# Adder.net
KiCad netlist of a schematic drawn in EAGLE
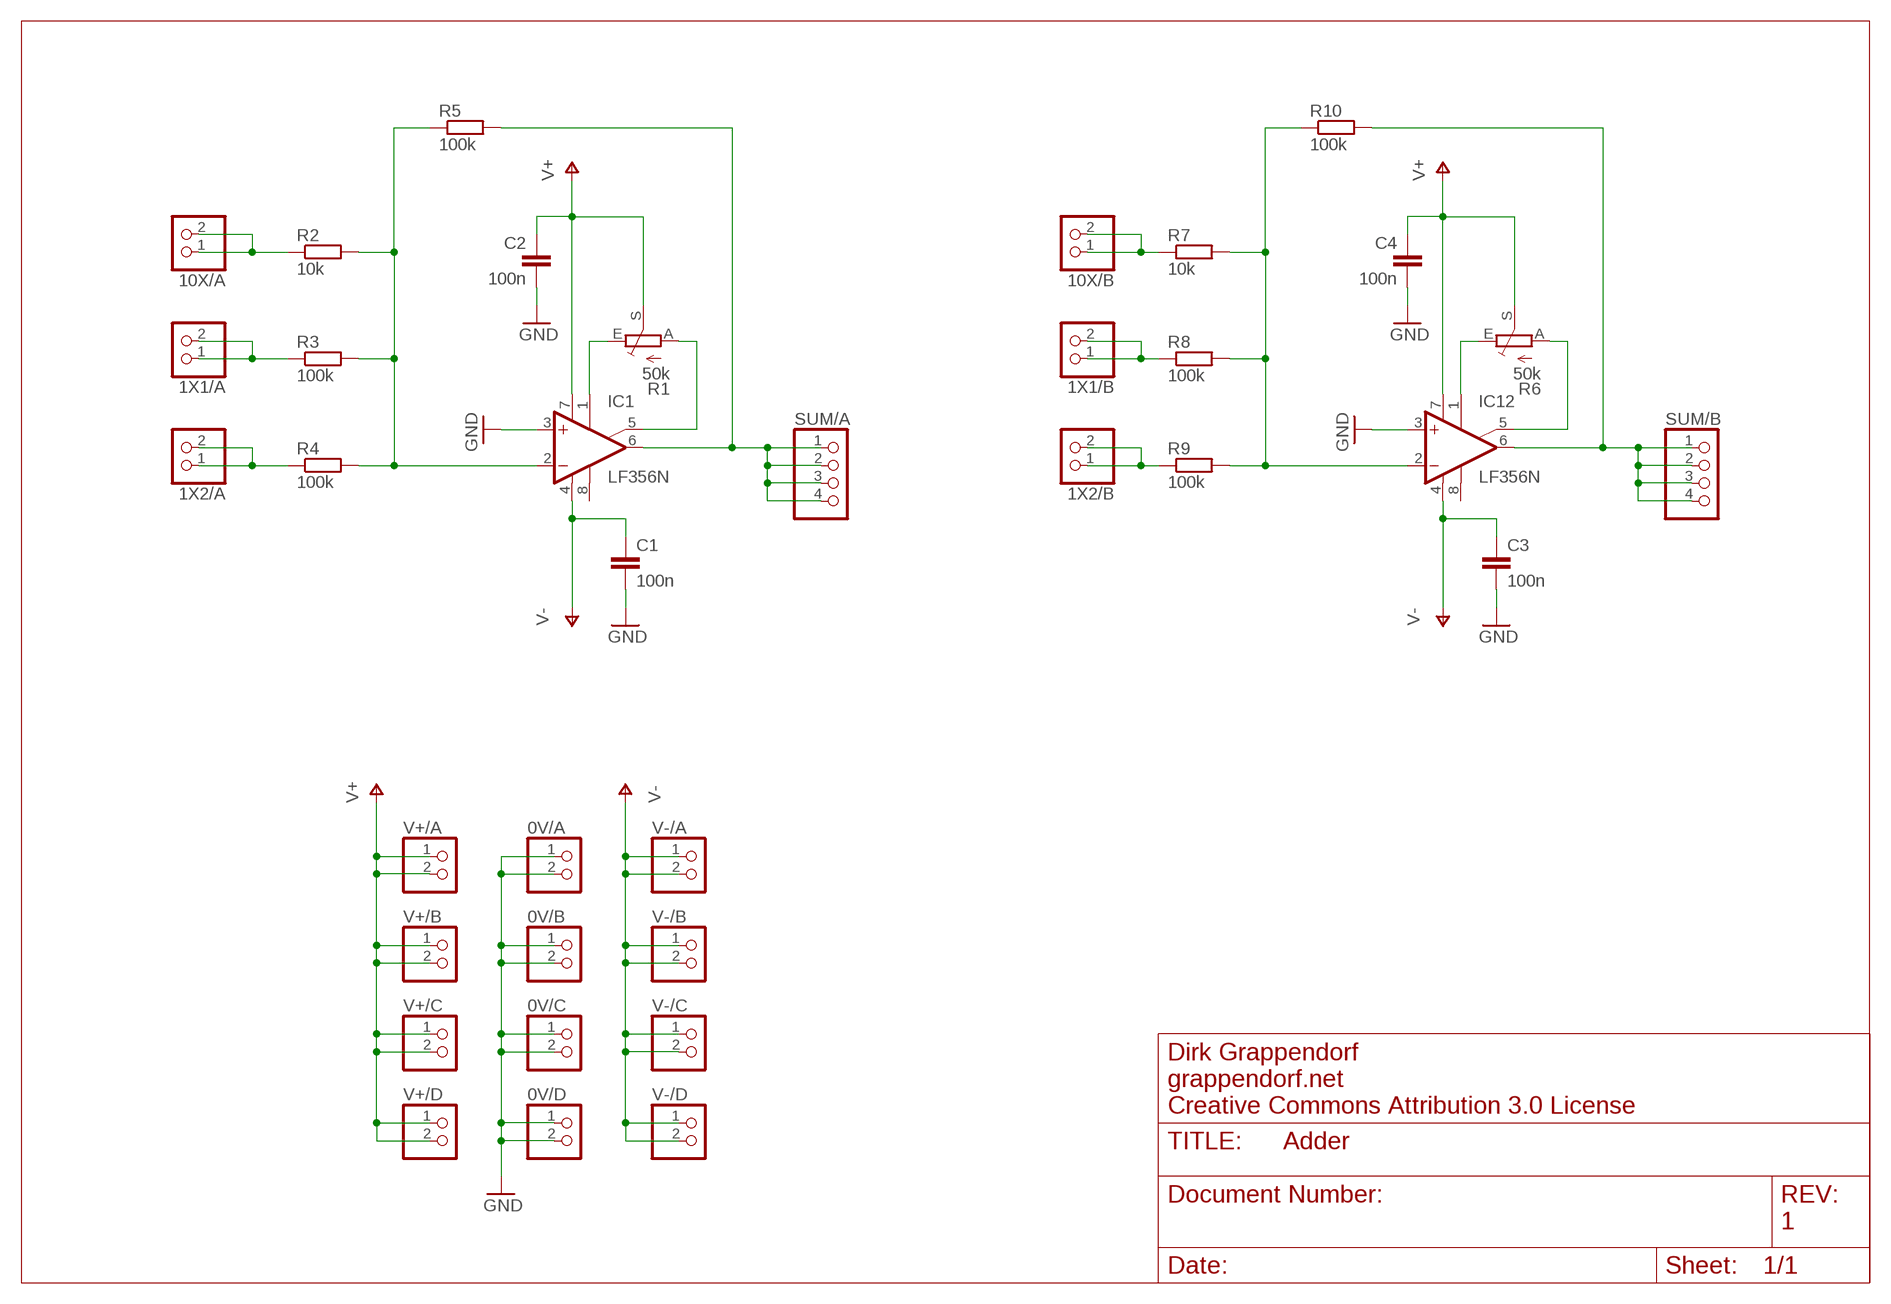
[diagram p0: schematic, sheet 1]

(export (version "E")
  (design (tool "Eeschema 10.0.6"))
  (components
    (comp (ref "0V/A")
      (value "PINHD-1X2")
      (footprint "eagle-import:1X02")
      (libsource (lib "eagle-import") (part "PINHD-1X2"))
    )
    (comp (ref "0V/B")
      (value "PINHD-1X2")
      (footprint "eagle-import:1X02")
      (libsource (lib "eagle-import") (part "PINHD-1X2"))
    )
    (comp (ref "0V/C")
      (value "PINHD-1X2")
      (footprint "eagle-import:1X02")
      (libsource (lib "eagle-import") (part "PINHD-1X2"))
    )
    (comp (ref "0V/D")
      (value "PINHD-1X2")
      (footprint "eagle-import:1X02")
      (libsource (lib "eagle-import") (part "PINHD-1X2"))
    )
    (comp (ref "1X1/A")
      (value "PINHD-1X2")
      (footprint "eagle-import:1X02")
      (libsource (lib "eagle-import") (part "PINHD-1X2"))
    )
    (comp (ref "1X1/B")
      (value "PINHD-1X2")
      (footprint "eagle-import:1X02")
      (libsource (lib "eagle-import") (part "PINHD-1X2"))
    )
    (comp (ref "1X2/A")
      (value "PINHD-1X2")
      (footprint "eagle-import:1X02")
      (libsource (lib "eagle-import") (part "PINHD-1X2"))
    )
    (comp (ref "1X2/B")
      (value "PINHD-1X2")
      (footprint "eagle-import:1X02")
      (libsource (lib "eagle-import") (part "PINHD-1X2"))
    )
    (comp (ref "10X/A")
      (value "PINHD-1X2")
      (footprint "eagle-import:1X02")
      (libsource (lib "eagle-import") (part "PINHD-1X2"))
    )
    (comp (ref "10X/B")
      (value "PINHD-1X2")
      (footprint "eagle-import:1X02")
      (libsource (lib "eagle-import") (part "PINHD-1X2"))
    )
    (comp (ref "C1")
      (value "100n")
      (footprint "eagle-import:C025-025X050")
      (libsource (lib "eagle-import") (part "C-EU025-025X050"))
    )
    (comp (ref "C2")
      (value "100n")
      (footprint "eagle-import:C025-025X050")
      (libsource (lib "eagle-import") (part "C-EU025-025X050"))
    )
    (comp (ref "C3")
      (value "100n")
      (footprint "eagle-import:C025-025X050")
      (libsource (lib "eagle-import") (part "C-EU025-025X050"))
    )
    (comp (ref "C4")
      (value "100n")
      (footprint "eagle-import:C025-025X050")
      (libsource (lib "eagle-import") (part "C-EU025-025X050"))
    )
    (comp (ref "IC1")
      (value "LF356N")
      (footprint "eagle-import:DIL08")
      (libsource (lib "eagle-import") (part "LF356N"))
    )
    (comp (ref "IC12")
      (value "LF356N")
      (footprint "eagle-import:DIL08")
      (libsource (lib "eagle-import") (part "LF356N"))
    )
    (comp (ref "R1")
      (value "50k")
      (footprint "eagle-import:LI15")
      (libsource (lib "eagle-import") (part "TRIM_EU-LI15"))
    )
    (comp (ref "R2")
      (value "10k")
      (footprint "eagle-import:0207_7")
      (libsource (lib "eagle-import") (part "R-EU_0207/7"))
    )
    (comp (ref "R3")
      (value "100k")
      (footprint "eagle-import:0207_7")
      (libsource (lib "eagle-import") (part "R-EU_0207/7"))
    )
    (comp (ref "R4")
      (value "100k")
      (footprint "eagle-import:0207_7")
      (libsource (lib "eagle-import") (part "R-EU_0207/7"))
    )
    (comp (ref "R5")
      (value "100k")
      (footprint "eagle-import:0207_7")
      (libsource (lib "eagle-import") (part "R-EU_0207/7"))
    )
    (comp (ref "R6")
      (value "50k")
      (footprint "eagle-import:LI15")
      (libsource (lib "eagle-import") (part "TRIM_EU-LI15"))
    )
    (comp (ref "R7")
      (value "10k")
      (footprint "eagle-import:0207_7")
      (libsource (lib "eagle-import") (part "R-EU_0207/7"))
    )
    (comp (ref "R8")
      (value "100k")
      (footprint "eagle-import:0207_7")
      (libsource (lib "eagle-import") (part "R-EU_0207/7"))
    )
    (comp (ref "R9")
      (value "100k")
      (footprint "eagle-import:0207_7")
      (libsource (lib "eagle-import") (part "R-EU_0207/7"))
    )
    (comp (ref "R10")
      (value "100k")
      (footprint "eagle-import:0207_7")
      (libsource (lib "eagle-import") (part "R-EU_0207/7"))
    )
    (comp (ref "SUM/A")
      (value "PINHD-1X4")
      (footprint "eagle-import:1X04")
      (libsource (lib "eagle-import") (part "PINHD-1X4"))
    )
    (comp (ref "SUM/B")
      (value "PINHD-1X4")
      (footprint "eagle-import:1X04")
      (libsource (lib "eagle-import") (part "PINHD-1X4"))
    )
    (comp (ref "V+/A")
      (value "PINHD-1X2")
      (footprint "eagle-import:1X02")
      (libsource (lib "eagle-import") (part "PINHD-1X2"))
    )
    (comp (ref "V+/B")
      (value "PINHD-1X2")
      (footprint "eagle-import:1X02")
      (libsource (lib "eagle-import") (part "PINHD-1X2"))
    )
    (comp (ref "V+/C")
      (value "PINHD-1X2")
      (footprint "eagle-import:1X02")
      (libsource (lib "eagle-import") (part "PINHD-1X2"))
    )
    (comp (ref "V+/D")
      (value "PINHD-1X2")
      (footprint "eagle-import:1X02")
      (libsource (lib "eagle-import") (part "PINHD-1X2"))
    )
    (comp (ref "V-/A")
      (value "PINHD-1X2")
      (footprint "eagle-import:1X02")
      (libsource (lib "eagle-import") (part "PINHD-1X2"))
    )
    (comp (ref "V-/B")
      (value "PINHD-1X2")
      (footprint "eagle-import:1X02")
      (libsource (lib "eagle-import") (part "PINHD-1X2"))
    )
    (comp (ref "V-/C")
      (value "PINHD-1X2")
      (footprint "eagle-import:1X02")
      (libsource (lib "eagle-import") (part "PINHD-1X2"))
    )
    (comp (ref "V-/D")
      (value "PINHD-1X2")
      (footprint "eagle-import:1X02")
      (libsource (lib "eagle-import") (part "PINHD-1X2"))
    )
  )
  (nets
    (net (code "1") (name "GND") (class "Default")
      (node (ref "0V/A") (pin "1") (pinfunction "1_1") (pintype "passive"))
      (node (ref "0V/A") (pin "2") (pinfunction "2_2") (pintype "passive"))
      (node (ref "0V/B") (pin "1") (pinfunction "1_1") (pintype "passive"))
      (node (ref "0V/B") (pin "2") (pinfunction "2_2") (pintype "passive"))
      (node (ref "0V/C") (pin "1") (pinfunction "1_1") (pintype "passive"))
      (node (ref "0V/C") (pin "2") (pinfunction "2_2") (pintype "passive"))
      (node (ref "0V/D") (pin "1") (pinfunction "1_1") (pintype "passive"))
      (node (ref "0V/D") (pin "2") (pinfunction "2_2") (pintype "passive"))
      (node (ref "C1") (pin "2") (pinfunction "2_2") (pintype "passive"))
      (node (ref "C2") (pin "2") (pinfunction "2_2") (pintype "passive"))
      (node (ref "C3") (pin "2") (pinfunction "2_2") (pintype "passive"))
      (node (ref "C4") (pin "2") (pinfunction "2_2") (pintype "passive"))
      (node (ref "IC1") (pin "3") (pinfunction "+IN_3") (pintype "input"))
      (node (ref "IC12") (pin "3") (pinfunction "+IN_3") (pintype "input"))
    )
    (net (code "2") (name "Net-(1X1/A-Pad1)") (class "Default")
      (node (ref "1X1/A") (pin "1") (pinfunction "1_1") (pintype "passive"))
      (node (ref "1X1/A") (pin "2") (pinfunction "2_2") (pintype "passive"))
      (node (ref "R3") (pin "1") (pinfunction "1_1") (pintype "passive"))
    )
    (net (code "3") (name "Net-(1X1/B-Pad1)") (class "Default")
      (node (ref "1X1/B") (pin "1") (pinfunction "1_1") (pintype "passive"))
      (node (ref "1X1/B") (pin "2") (pinfunction "2_2") (pintype "passive"))
      (node (ref "R8") (pin "1") (pinfunction "1_1") (pintype "passive"))
    )
    (net (code "4") (name "Net-(1X2/A-Pad1)") (class "Default")
      (node (ref "1X2/A") (pin "1") (pinfunction "1_1") (pintype "passive"))
      (node (ref "1X2/A") (pin "2") (pinfunction "2_2") (pintype "passive"))
      (node (ref "R4") (pin "1") (pinfunction "1_1") (pintype "passive"))
    )
    (net (code "5") (name "Net-(1X2/B-Pad1)") (class "Default")
      (node (ref "1X2/B") (pin "1") (pinfunction "1_1") (pintype "passive"))
      (node (ref "1X2/B") (pin "2") (pinfunction "2_2") (pintype "passive"))
      (node (ref "R9") (pin "1") (pinfunction "1_1") (pintype "passive"))
    )
    (net (code "6") (name "Net-(10X/A-Pad1)") (class "Default")
      (node (ref "10X/A") (pin "1") (pinfunction "1_1") (pintype "passive"))
      (node (ref "10X/A") (pin "2") (pinfunction "2_2") (pintype "passive"))
      (node (ref "R2") (pin "1") (pinfunction "1_1") (pintype "passive"))
    )
    (net (code "7") (name "Net-(10X/B-Pad1)") (class "Default")
      (node (ref "10X/B") (pin "1") (pinfunction "1_1") (pintype "passive"))
      (node (ref "10X/B") (pin "2") (pinfunction "2_2") (pintype "passive"))
      (node (ref "R7") (pin "1") (pinfunction "1_1") (pintype "passive"))
    )
    (net (code "8") (name "Net-(IC1--IN)") (class "Default")
      (node (ref "IC1") (pin "2") (pinfunction "-IN_2") (pintype "input"))
      (node (ref "R2") (pin "2") (pinfunction "2_2") (pintype "passive"))
      (node (ref "R3") (pin "2") (pinfunction "2_2") (pintype "passive"))
      (node (ref "R4") (pin "2") (pinfunction "2_2") (pintype "passive"))
      (node (ref "R5") (pin "1") (pinfunction "1_1") (pintype "passive"))
    )
    (net (code "9") (name "Net-(IC1-ON1)") (class "Default")
      (node (ref "IC1") (pin "1") (pinfunction "ON1_1") (pintype "passive"))
      (node (ref "R1") (pin "E") (pinfunction "E_E") (pintype "passive"))
    )
    (net (code "10") (name "Net-(IC1-ON2)") (class "Default")
      (node (ref "IC1") (pin "5") (pinfunction "ON2_5") (pintype "passive"))
      (node (ref "R1") (pin "A") (pinfunction "A_A") (pintype "passive"))
    )
    (net (code "11") (name "Net-(IC1-OUT)") (class "Default")
      (node (ref "IC1") (pin "6") (pinfunction "OUT_6") (pintype "output"))
      (node (ref "R5") (pin "2") (pinfunction "2_2") (pintype "passive"))
      (node (ref "SUM/A") (pin "1") (pinfunction "1_1") (pintype "passive"))
      (node (ref "SUM/A") (pin "2") (pinfunction "2_2") (pintype "passive"))
      (node (ref "SUM/A") (pin "3") (pinfunction "3_3") (pintype "passive"))
      (node (ref "SUM/A") (pin "4") (pinfunction "4_4") (pintype "passive"))
    )
    (net (code "12") (name "Net-(IC12--IN)") (class "Default")
      (node (ref "IC12") (pin "2") (pinfunction "-IN_2") (pintype "input"))
      (node (ref "R10") (pin "1") (pinfunction "1_1") (pintype "passive"))
      (node (ref "R7") (pin "2") (pinfunction "2_2") (pintype "passive"))
      (node (ref "R8") (pin "2") (pinfunction "2_2") (pintype "passive"))
      (node (ref "R9") (pin "2") (pinfunction "2_2") (pintype "passive"))
    )
    (net (code "13") (name "Net-(IC12-ON1)") (class "Default")
      (node (ref "IC12") (pin "1") (pinfunction "ON1_1") (pintype "passive"))
      (node (ref "R6") (pin "E") (pinfunction "E_E") (pintype "passive"))
    )
    (net (code "14") (name "Net-(IC12-ON2)") (class "Default")
      (node (ref "IC12") (pin "5") (pinfunction "ON2_5") (pintype "passive"))
      (node (ref "R6") (pin "A") (pinfunction "A_A") (pintype "passive"))
    )
    (net (code "15") (name "Net-(IC12-OUT)") (class "Default")
      (node (ref "IC12") (pin "6") (pinfunction "OUT_6") (pintype "output"))
      (node (ref "R10") (pin "2") (pinfunction "2_2") (pintype "passive"))
      (node (ref "SUM/B") (pin "1") (pinfunction "1_1") (pintype "passive"))
      (node (ref "SUM/B") (pin "2") (pinfunction "2_2") (pintype "passive"))
      (node (ref "SUM/B") (pin "3") (pinfunction "3_3") (pintype "passive"))
      (node (ref "SUM/B") (pin "4") (pinfunction "4_4") (pintype "passive"))
    )
    (net (code "16") (name "V+") (class "Default")
      (node (ref "C2") (pin "1") (pinfunction "1_1") (pintype "passive"))
      (node (ref "C4") (pin "1") (pinfunction "1_1") (pintype "passive"))
      (node (ref "IC1") (pin "7") (pinfunction "V+_7") (pintype "power_in"))
      (node (ref "IC12") (pin "7") (pinfunction "V+_7") (pintype "power_in"))
      (node (ref "R1") (pin "S") (pinfunction "S_S") (pintype "passive"))
      (node (ref "R6") (pin "S") (pinfunction "S_S") (pintype "passive"))
      (node (ref "V+/A") (pin "1") (pinfunction "1_1") (pintype "passive"))
      (node (ref "V+/A") (pin "2") (pinfunction "2_2") (pintype "passive"))
      (node (ref "V+/B") (pin "1") (pinfunction "1_1") (pintype "passive"))
      (node (ref "V+/B") (pin "2") (pinfunction "2_2") (pintype "passive"))
      (node (ref "V+/C") (pin "1") (pinfunction "1_1") (pintype "passive"))
      (node (ref "V+/C") (pin "2") (pinfunction "2_2") (pintype "passive"))
      (node (ref "V+/D") (pin "1") (pinfunction "1_1") (pintype "passive"))
      (node (ref "V+/D") (pin "2") (pinfunction "2_2") (pintype "passive"))
    )
    (net (code "17") (name "V-") (class "Default")
      (node (ref "C1") (pin "1") (pinfunction "1_1") (pintype "passive"))
      (node (ref "C3") (pin "1") (pinfunction "1_1") (pintype "passive"))
      (node (ref "IC1") (pin "4") (pinfunction "V-_4") (pintype "power_in"))
      (node (ref "IC12") (pin "4") (pinfunction "V-_4") (pintype "power_in"))
      (node (ref "V-/A") (pin "1") (pinfunction "1_1") (pintype "passive"))
      (node (ref "V-/A") (pin "2") (pinfunction "2_2") (pintype "passive"))
      (node (ref "V-/B") (pin "1") (pinfunction "1_1") (pintype "passive"))
      (node (ref "V-/B") (pin "2") (pinfunction "2_2") (pintype "passive"))
      (node (ref "V-/C") (pin "1") (pinfunction "1_1") (pintype "passive"))
      (node (ref "V-/C") (pin "2") (pinfunction "2_2") (pintype "passive"))
      (node (ref "V-/D") (pin "1") (pinfunction "1_1") (pintype "passive"))
      (node (ref "V-/D") (pin "2") (pinfunction "2_2") (pintype "passive"))
    )
    (net (code "18") (name "unconnected-(IC1-OPT-Pad8)") (class "Default")
      (node (ref "IC1") (pin "8") (pinfunction "OPT_8") (pintype "passive"))
    )
    (net (code "19") (name "unconnected-(IC12-OPT-Pad8)") (class "Default")
      (node (ref "IC12") (pin "8") (pinfunction "OPT_8") (pintype "passive"))
    )
  )
)
